# OpenRing_Temperature.net
KiCad netlist of a schematic drawn in Altium Designer
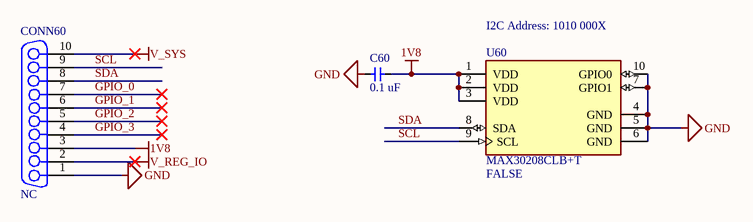
[diagram p0: OpenRing_Temperature.SchDoc]

(export (version "E")
  (design (tool "Eeschema 10.0.6"))
  (components
    (comp (ref "C60")
      (value "0.1 uF")
      (footprint "CAPC1005X05N")
      (description "CAP CER 0.1UF 16V X5R 0402")
      (fields
        (field (name "MANUFACTURER") "Murata Electronics")
        (field (name "MANUFACTURER PART NUMBER") "GRM155R61C104KA88D")
      )
      (libsource (lib "OpenRingComponents") (part "GRM155R61C104KA88D"))
    )
    (comp (ref "CONN60")
      (value "NC")
      (footprint "51281-1098-PCB")
      (libsource (lib "Connectors") (part "51281-1098-PCB"))
    )
    (comp (ref "U60")
      (value "MAX30208CLB+T")
      (footprint "FP-L1022-2-MFG")
      (description "I2C Digital Temperature Sensor Serial I2C 10-Pin Thin LGA T/R")
      (fields (field (name "MANUFACTURER") "Maxim") (field (name "CHECKED") "FALSE"))
      (libsource (lib "OpenRingComponents") (part "MAX30208CLB+T"))
    )
  )
  (nets
    (net (code "1") (name "/GPIO_0") (class "Default")
      (node (ref "CONN60") (pin "7") (pinfunction "7_7") (pintype "passive+no_connect"))
    )
    (net (code "2") (name "/GPIO_1") (class "Default")
      (node (ref "CONN60") (pin "6") (pinfunction "6_6") (pintype "passive+no_connect"))
    )
    (net (code "3") (name "/GPIO_2") (class "Default")
      (node (ref "CONN60") (pin "5") (pinfunction "5_5") (pintype "passive+no_connect"))
    )
    (net (code "4") (name "/GPIO_3") (class "Default")
      (node (ref "CONN60") (pin "4") (pinfunction "4_4") (pintype "passive+no_connect"))
    )
    (net (code "5") (name "/SCL") (class "Default")
      (node (ref "CONN60") (pin "9") (pinfunction "9_9") (pintype "passive"))
      (node (ref "U60") (pin "9") (pinfunction "SCL_9") (pintype "input"))
    )
    (net (code "6") (name "/SDA") (class "Default")
      (node (ref "CONN60") (pin "8") (pinfunction "8_8") (pintype "passive"))
      (node (ref "U60") (pin "8") (pinfunction "SDA_8") (pintype "bidirectional"))
    )
    (net (code "7") (name "1V8") (class "Default")
      (node (ref "C60") (pin "1") (pinfunction "1_1") (pintype "passive"))
      (node (ref "CONN60") (pin "3") (pinfunction "3_3") (pintype "passive"))
      (node (ref "U60") (pin "1") (pinfunction "VDD_1") (pintype "power_in"))
      (node (ref "U60") (pin "2") (pinfunction "VDD_2") (pintype "power_in"))
      (node (ref "U60") (pin "3") (pinfunction "VDD_3") (pintype "power_in"))
    )
    (net (code "8") (name "GND") (class "Default")
      (node (ref "C60") (pin "2") (pinfunction "2_2") (pintype "passive"))
      (node (ref "CONN60") (pin "1") (pinfunction "1_1") (pintype "passive"))
      (node (ref "U60") (pin "10") (pinfunction "GPIO0_10") (pintype "bidirectional"))
      (node (ref "U60") (pin "4") (pinfunction "GND_4") (pintype "power_in"))
      (node (ref "U60") (pin "5") (pinfunction "GND_5") (pintype "power_in"))
      (node (ref "U60") (pin "6") (pinfunction "GND_6") (pintype "power_in"))
      (node (ref "U60") (pin "7") (pinfunction "GPIO1_7") (pintype "bidirectional"))
    )
    (net (code "9") (name "V_REG_IO") (class "Default")
      (node (ref "CONN60") (pin "2") (pinfunction "2_2") (pintype "passive"))
    )
    (net (code "10") (name "V_SYS") (class "Default")
      (node (ref "CONN60") (pin "10") (pinfunction "10_10") (pintype "passive"))
    )
  )
)
